# BMSv5_BatLength.net
KiCad netlist of a schematic drawn in EAGLE
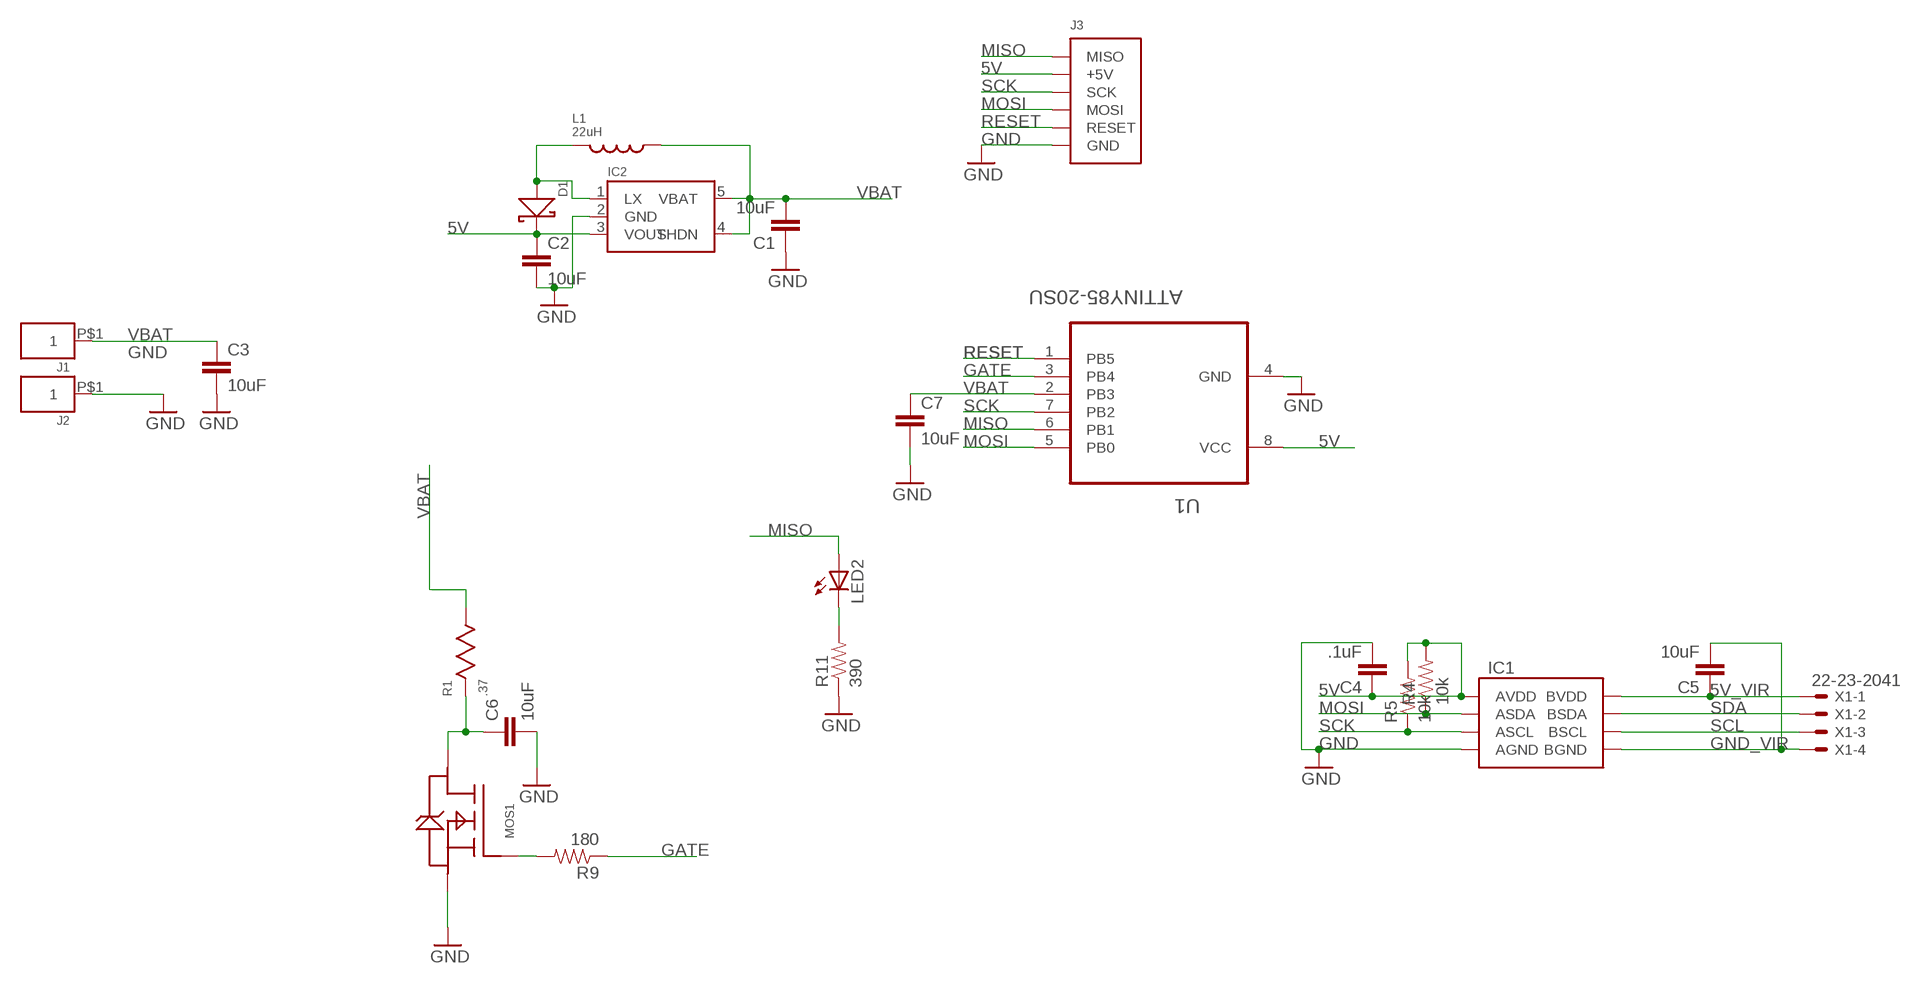
[diagram p0: schematic, sheet 1]

(export (version "E")
  (design (tool "Eeschema 10.0.6"))
  (components
    (comp (ref "C1")
      (value "10uF")
      (footprint "eagle-import:0805-CAP")
      (libsource (lib "eagle-import") (part "10UF10V10%(0805)"))
    )
    (comp (ref "C2")
      (value "10uF")
      (footprint "eagle-import:0805-CAP")
      (libsource (lib "eagle-import") (part "10UF10V10%(0805)"))
    )
    (comp (ref "C3")
      (value "10uF")
      (footprint "eagle-import:0805-CAP")
      (libsource (lib "eagle-import") (part "10UF10V10%(0805)"))
    )
    (comp (ref "C4")
      (value ".1uF")
      (footprint "eagle-import:0805-CAP")
      (libsource (lib "eagle-import") (part "10UF10V10%(0805)"))
    )
    (comp (ref "C5")
      (value "10uF")
      (footprint "eagle-import:0805-CAP")
      (libsource (lib "eagle-import") (part "10UF10V10%(0805)"))
    )
    (comp (ref "C6")
      (value "10uF")
      (footprint "eagle-import:0805-CAP")
      (libsource (lib "eagle-import") (part "10UF10V10%(0805)"))
    )
    (comp (ref "C7")
      (value "10uF")
      (footprint "eagle-import:0805-CAP")
      (libsource (lib "eagle-import") (part "10UF10V10%(0805)"))
    )
    (comp (ref "D1")
      (value "DIODE_SCHOTTKYSOD-123")
      (footprint "eagle-import:SOD-123")
      (libsource (lib "eagle-import") (part "DIODE_SCHOTTKYSOD-123"))
    )
    (comp (ref "IC1")
      (value "SI8600_DUALCHANNELISO")
      (footprint "eagle-import:SOIC-8")
      (libsource (lib "eagle-import") (part "SI8600_DUALCHANNELISO"))
    )
    (comp (ref "IC2")
      (value "SP6641")
      (footprint "eagle-import:SOT-23")
      (libsource (lib "eagle-import") (part "SP6641"))
    )
    (comp (ref "J1")
      (value "CONNECTOR_1PIN")
      (footprint "eagle-import:SMD_PAD_.15X.25")
      (libsource (lib "eagle-import") (part "CONNECTOR_1PIN"))
    )
    (comp (ref "J2")
      (value "CONNECTOR_1PIN")
      (footprint "eagle-import:SMD_PAD_.15X.25")
      (libsource (lib "eagle-import") (part "CONNECTOR_1PIN"))
    )
    (comp (ref "J3")
      (value "ISPHEADER")
      (footprint "eagle-import:2X3PIN_.1'")
      (libsource (lib "eagle-import") (part "ISPHEADER"))
    )
    (comp (ref "L1")
      (value "22uH")
      (footprint "eagle-import:6X6MM_IND")
      (libsource (lib "eagle-import") (part "CHIP_IND1"))
    )
    (comp (ref "LED2")
      (value "LEDCHIPLED_0805")
      (footprint "eagle-import:CHIPLED_0805")
      (libsource (lib "eagle-import") (part "LEDCHIPLED_0805"))
    )
    (comp (ref "MOS1")
      (value "MOS_N_LOGIC_PSMN7R0")
      (footprint "eagle-import:LFPAK")
      (libsource (lib "eagle-import") (part "MOS_N_LOGIC_PSMN7R0"))
    )
    (comp (ref "R1")
      (value ".37")
      (footprint "eagle-import:TO-220-2")
      (libsource (lib "eagle-import") (part "RES_THROUGH"))
    )
    (comp (ref "R4")
      (value "10k")
      (footprint "eagle-import:0805")
      (libsource (lib "eagle-import") (part "0.3OHM-1/8W-1%(0805)"))
    )
    (comp (ref "R5")
      (value "10k")
      (footprint "eagle-import:0805")
      (libsource (lib "eagle-import") (part "0.3OHM-1/8W-1%(0805)"))
    )
    (comp (ref "R9")
      (value "180")
      (footprint "eagle-import:0805")
      (libsource (lib "eagle-import") (part "0.3OHM-1/8W-1%(0805)"))
    )
    (comp (ref "R11")
      (value "390")
      (footprint "eagle-import:0805")
      (libsource (lib "eagle-import") (part "0.3OHM-1/8W-1%(0805)"))
    )
    (comp (ref "U1")
      (value "ATTINY85-20SU")
      (footprint "eagle-import:SOIC127P798X216-8N")
      (libsource (lib "eagle-import") (part "ATTINY85-20SU"))
    )
    (comp (ref "X1")
      (value "22-23-2041")
      (footprint "eagle-import:22-23-2041")
      (fields (field (name "MF") "MOLEX"))
      (libsource (lib "eagle-import") (part "22-23-2041"))
    )
  )
  (nets
    (net (code "1") (name "5V") (class "Default")
      (node (ref "C2") (pin "1") (pinfunction "1_1") (pintype "passive"))
      (node (ref "C4") (pin "1") (pinfunction "1_1") (pintype "passive"))
      (node (ref "D1") (pin "CATHODE") (pinfunction "CATHODE_CATHODE") (pintype "bidirectional"))
      (node (ref "IC1") (pin "P$1") (pinfunction "AVDD_P$1") (pintype "bidirectional"))
      (node (ref "IC2") (pin "3") (pinfunction "VOUT_3") (pintype "bidirectional"))
      (node (ref "J3") (pin "P$2") (pinfunction "+5V_P$2") (pintype "bidirectional"))
      (node (ref "R4") (pin "2") (pinfunction "2_2") (pintype "passive"))
      (node (ref "R5") (pin "2") (pinfunction "2_2") (pintype "passive"))
      (node (ref "U1") (pin "8") (pinfunction "VCC_8") (pintype "power_in"))
    )
    (net (code "2") (name "5V_VIR") (class "Default")
      (node (ref "C5") (pin "1") (pinfunction "1_1") (pintype "passive"))
      (node (ref "IC1") (pin "P$8") (pinfunction "BVDD_P$8") (pintype "bidirectional"))
      (node (ref "X1") (pin "1") (pinfunction "S_1") (pintype "passive"))
    )
    (net (code "3") (name "GATE") (class "Default")
      (node (ref "R9") (pin "1") (pinfunction "1_1") (pintype "passive"))
      (node (ref "U1") (pin "3") (pinfunction "PB4_3") (pintype "bidirectional"))
    )
    (net (code "4") (name "GND") (class "Default")
      (node (ref "C1") (pin "1") (pinfunction "1_1") (pintype "passive"))
      (node (ref "C2") (pin "2") (pinfunction "2_2") (pintype "passive"))
      (node (ref "C3") (pin "2") (pinfunction "2_2") (pintype "passive"))
      (node (ref "C4") (pin "2") (pinfunction "2_2") (pintype "passive"))
      (node (ref "C6") (pin "2") (pinfunction "2_2") (pintype "passive"))
      (node (ref "C7") (pin "2") (pinfunction "2_2") (pintype "passive"))
      (node (ref "IC1") (pin "P$4") (pinfunction "AGND_P$4") (pintype "bidirectional"))
      (node (ref "IC2") (pin "2") (pinfunction "GND_2") (pintype "bidirectional"))
      (node (ref "J2") (pin "P$1") (pinfunction "1_P$1") (pintype "bidirectional"))
      (node (ref "J3") (pin "P$6") (pinfunction "GND_P$6") (pintype "bidirectional"))
      (node (ref "MOS1") (pin "P$1") (pinfunction "SOURCE_P$1") (pintype "bidirectional"))
      (node (ref "MOS1") (pin "P$2") (pinfunction "SOURCE_P$2") (pintype "bidirectional"))
      (node (ref "MOS1") (pin "P$3") (pinfunction "SOURCE_P$3") (pintype "bidirectional"))
      (node (ref "R11") (pin "1") (pinfunction "1_1") (pintype "passive"))
      (node (ref "U1") (pin "4") (pinfunction "GND_4") (pintype "passive"))
    )
    (net (code "5") (name "GND_VIR") (class "Default")
      (node (ref "C5") (pin "2") (pinfunction "2_2") (pintype "passive"))
      (node (ref "IC1") (pin "P$5") (pinfunction "BGND_P$5") (pintype "bidirectional"))
      (node (ref "X1") (pin "4") (pinfunction "S_4") (pintype "passive"))
    )
    (net (code "6") (name "MISO") (class "Default")
      (node (ref "J3") (pin "P$1") (pinfunction "MISO_P$1") (pintype "bidirectional"))
      (node (ref "LED2") (pin "A") (pinfunction "A_A") (pintype "passive"))
      (node (ref "U1") (pin "6") (pinfunction "PB1_6") (pintype "bidirectional"))
    )
    (net (code "7") (name "MOSI") (class "Default")
      (node (ref "IC1") (pin "P$2") (pinfunction "ASDA_P$2") (pintype "bidirectional"))
      (node (ref "J3") (pin "P$4") (pinfunction "MOSI_P$4") (pintype "bidirectional"))
      (node (ref "R4") (pin "1") (pinfunction "1_1") (pintype "passive"))
      (node (ref "U1") (pin "5") (pinfunction "PB0_5") (pintype "bidirectional"))
    )
    (net (code "8") (name "Net-(IC2-LX)") (class "Default")
      (node (ref "D1") (pin "ANODE") (pinfunction "ANODE_ANODE") (pintype "bidirectional"))
      (node (ref "IC2") (pin "1") (pinfunction "LX_1") (pintype "bidirectional"))
      (node (ref "L1") (pin "P$1") (pinfunction "P$1_P$1") (pintype "bidirectional"))
    )
    (net (code "9") (name "Net-(LED2-PadC)") (class "Default")
      (node (ref "LED2") (pin "C") (pinfunction "C_C") (pintype "passive"))
      (node (ref "R11") (pin "2") (pinfunction "2_2") (pintype "passive"))
    )
    (net (code "10") (name "Net-(MOS1-DRAIN)") (class "Default")
      (node (ref "C6") (pin "1") (pinfunction "1_1") (pintype "passive"))
      (node (ref "MOS1") (pin "P$5") (pinfunction "DRAIN_P$5") (pintype "bidirectional"))
      (node (ref "R1") (pin "P$1") (pinfunction "P$1_P$1") (pintype "bidirectional"))
    )
    (net (code "11") (name "Net-(MOS1-GATE)") (class "Default")
      (node (ref "MOS1") (pin "P$4") (pinfunction "GATE_P$4") (pintype "bidirectional"))
      (node (ref "R9") (pin "2") (pinfunction "2_2") (pintype "passive"))
    )
    (net (code "12") (name "RESET") (class "Default")
      (node (ref "J3") (pin "P$5") (pinfunction "RESET_P$5") (pintype "bidirectional"))
      (node (ref "U1") (pin "1") (pinfunction "PB5_1") (pintype "bidirectional"))
    )
    (net (code "13") (name "SCK") (class "Default")
      (node (ref "IC1") (pin "P$3") (pinfunction "ASCL_P$3") (pintype "bidirectional"))
      (node (ref "J3") (pin "P$3") (pinfunction "SCK_P$3") (pintype "bidirectional"))
      (node (ref "R5") (pin "1") (pinfunction "1_1") (pintype "passive"))
      (node (ref "U1") (pin "7") (pinfunction "PB2_7") (pintype "bidirectional"))
    )
    (net (code "14") (name "SCL") (class "Default")
      (node (ref "IC1") (pin "P$6") (pinfunction "BSCL_P$6") (pintype "bidirectional"))
      (node (ref "X1") (pin "3") (pinfunction "S_3") (pintype "passive"))
    )
    (net (code "15") (name "SDA") (class "Default")
      (node (ref "IC1") (pin "P$7") (pinfunction "BSDA_P$7") (pintype "bidirectional"))
      (node (ref "X1") (pin "2") (pinfunction "S_2") (pintype "passive"))
    )
    (net (code "16") (name "VBAT") (class "Default")
      (node (ref "C1") (pin "2") (pinfunction "2_2") (pintype "passive"))
      (node (ref "C3") (pin "1") (pinfunction "1_1") (pintype "passive"))
      (node (ref "C7") (pin "1") (pinfunction "1_1") (pintype "passive"))
      (node (ref "IC2") (pin "4") (pinfunction "SHDN_4") (pintype "bidirectional"))
      (node (ref "IC2") (pin "5") (pinfunction "VBAT_5") (pintype "bidirectional"))
      (node (ref "J1") (pin "P$1") (pinfunction "1_P$1") (pintype "bidirectional"))
      (node (ref "L1") (pin "P$2") (pinfunction "P$2_P$2") (pintype "bidirectional"))
      (node (ref "R1") (pin "P$2") (pinfunction "P$2_P$2") (pintype "bidirectional"))
      (node (ref "U1") (pin "2") (pinfunction "PB3_2") (pintype "bidirectional"))
    )
  )
)
